# 4_color_LED.net
KiCad netlist of a schematic drawn in EAGLE
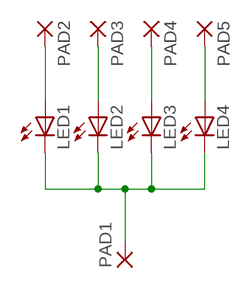
[diagram p0: schematic, sheet 1]

(export (version "E")
  (design (tool "Eeschema 10.0.6"))
  (components
    (comp (ref "LED1")
      (value "LEDCHIPLED_0805")
      (footprint "eagle-import:CHIPLED_0805")
      (libsource (lib "eagle-import") (part "LEDCHIPLED_0805"))
    )
    (comp (ref "LED2")
      (value "LEDCHIPLED_0805")
      (footprint "eagle-import:CHIPLED_0805")
      (libsource (lib "eagle-import") (part "LEDCHIPLED_0805"))
    )
    (comp (ref "LED3")
      (value "LEDCHIPLED_0805")
      (footprint "eagle-import:CHIPLED_0805")
      (libsource (lib "eagle-import") (part "LEDCHIPLED_0805"))
    )
    (comp (ref "LED4")
      (value "LEDCHIPLED_0805")
      (footprint "eagle-import:CHIPLED_0805")
      (libsource (lib "eagle-import") (part "LEDCHIPLED_0805"))
    )
    (comp (ref "PAD1")
      (value "1,6/0,8")
      (footprint "eagle-import:1,6_0,8")
      (libsource (lib "eagle-import") (part "1,6/0,8"))
    )
    (comp (ref "PAD2")
      (value "1,6/0,8")
      (footprint "eagle-import:1,6_0,8")
      (libsource (lib "eagle-import") (part "1,6/0,8"))
    )
    (comp (ref "PAD3")
      (value "1,6/0,8")
      (footprint "eagle-import:1,6_0,8")
      (libsource (lib "eagle-import") (part "1,6/0,8"))
    )
    (comp (ref "PAD4")
      (value "1,6/0,8")
      (footprint "eagle-import:1,6_0,8")
      (libsource (lib "eagle-import") (part "1,6/0,8"))
    )
    (comp (ref "PAD5")
      (value "1,6/0,8")
      (footprint "eagle-import:1,6_0,8")
      (libsource (lib "eagle-import") (part "1,6/0,8"))
    )
  )
  (nets
    (net (code "1") (name "Net-(PAD1-P)") (class "Default")
      (node (ref "LED1") (pin "C") (pinfunction "C_C") (pintype "passive"))
      (node (ref "LED2") (pin "C") (pinfunction "C_C") (pintype "passive"))
      (node (ref "LED3") (pin "C") (pinfunction "C_C") (pintype "passive"))
      (node (ref "LED4") (pin "C") (pinfunction "C_C") (pintype "passive"))
      (node (ref "PAD1") (pin "1") (pinfunction "P_1") (pintype "passive"))
    )
    (net (code "2") (name "Net-(PAD2-P)") (class "Default")
      (node (ref "LED1") (pin "A") (pinfunction "A_A") (pintype "passive"))
      (node (ref "PAD2") (pin "1") (pinfunction "P_1") (pintype "passive"))
    )
    (net (code "3") (name "Net-(PAD3-P)") (class "Default")
      (node (ref "LED2") (pin "A") (pinfunction "A_A") (pintype "passive"))
      (node (ref "PAD3") (pin "1") (pinfunction "P_1") (pintype "passive"))
    )
    (net (code "4") (name "Net-(PAD4-P)") (class "Default")
      (node (ref "LED3") (pin "A") (pinfunction "A_A") (pintype "passive"))
      (node (ref "PAD4") (pin "1") (pinfunction "P_1") (pintype "passive"))
    )
    (net (code "5") (name "Net-(PAD5-P)") (class "Default")
      (node (ref "LED4") (pin "A") (pinfunction "A_A") (pintype "passive"))
      (node (ref "PAD5") (pin "1") (pinfunction "P_1") (pintype "passive"))
    )
  )
)
